# Mopq.net
KiCad netlist of a schematic drawn in Altium Designer
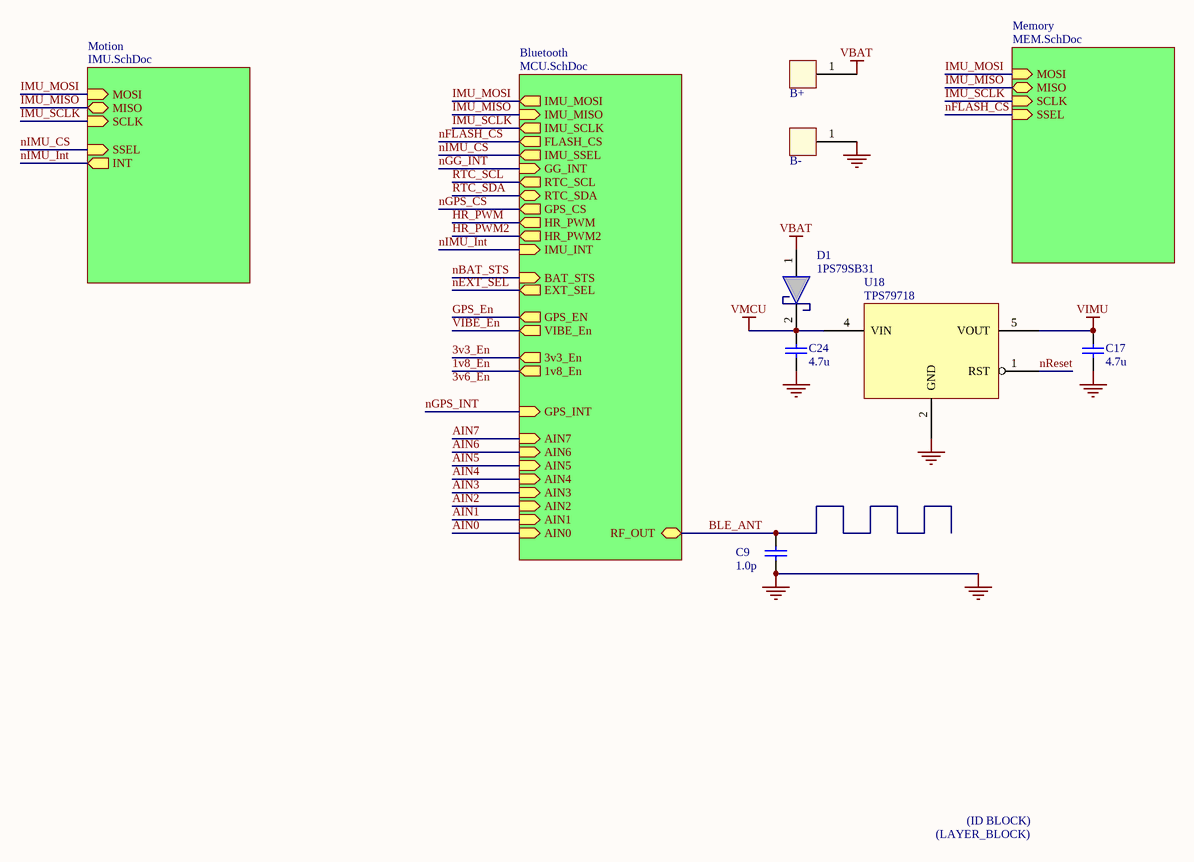
[diagram p0: Mopq.SchDoc]

(export (version "E")
  (design (tool "Eeschema 10.0.6"))
  (components
    (comp (ref "*")
      (value "LAYER_BLOCK")
      (footprint "Layer Stackup")
      (libsource (lib "Hello") (part "LAYER_BLOCK"))
    )
    (comp (ref "B+")
      (value "5016")
      (footprint "TP0875x050")
      (description "Single-pad test point")
      (libsource (lib "Mopd") (part "5016"))
    )
    (comp (ref "B-")
      (value "5016")
      (footprint "TP0875x050")
      (description "Single-pad test point")
      (libsource (lib "Mopd") (part "5016"))
    )
    (comp (ref "C9")
      (value "1.0p")
      (footprint "CAP0402")
      (description "Chip capacitor")
      (fields (field (name "TOLERANCE") "5 %") (field (name "VOLTAGE") "16V"))
      (libsource (lib "Hello") (part "C_2200p_5_16_STD_0402"))
    )
    (comp (ref "C17")
      (value "4.7u")
      (footprint "CAP0402")
      (description "Chip capacitor")
      (fields (field (name "TOLERANCE") "10%") (field (name "VOLTAGE") "10V"))
      (libsource (lib "Hello") (part "C_4.7u_10_10_JB_0402"))
    )
    (comp (ref "C24")
      (value "4.7u")
      (footprint "CAP0402")
      (description "Chip capacitor")
      (fields (field (name "TOLERANCE") "10%") (field (name "VOLTAGE") "10V"))
      (libsource (lib "Hello") (part "C_4.7u_10_10_JB_0402"))
    )
    (comp (ref "D1")
      (value "1PS79SB31")
      (footprint "SOD-523")
      (description "Schottky diode, 30V 200mA")
      (libsource (lib "Hello") (part "1PS79SB31"))
    )
    (comp (ref "ID1") (value "ID_BLOCK") (footprint "Hello Band") (libsource (lib "Hello") (part "ID_BLOCK")))
    (comp (ref "U18")
      (value "TPS79718")
      (footprint "SOT65P212X110-5N")
      (description "LDO 1.8V SC70-5")
      (libsource (lib "dykes") (part "TPS79718DCK"))
    )
  )
  (nets
    (net (code "12") (name "/BLE_ANT") (class "Default")
      (node (ref "C9") (pin "2") (pinfunction "2_2") (pintype "passive"))
    )
    (net (code "30") (name "/nReset") (class "Default")
      (node (ref "U18") (pin "1") (pinfunction "RST_1") (pintype "open_collector"))
    )
    (net (code "31") (name "GND") (class "Default")
      (node (ref "B-") (pin "1") (pinfunction "1_1") (pintype "passive"))
      (node (ref "C17") (pin "1") (pinfunction "1_1") (pintype "passive"))
      (node (ref "C24") (pin "1") (pinfunction "1_1") (pintype "passive"))
      (node (ref "C9") (pin "1") (pinfunction "1_1") (pintype "passive"))
      (node (ref "U18") (pin "2") (pinfunction "GND_2") (pintype "power_in"))
    )
    (net (code "32") (name "VBAT") (class "Default")
      (node (ref "B+") (pin "1") (pinfunction "1_1") (pintype "passive"))
      (node (ref "D1") (pin "1") (pinfunction "Anode_1") (pintype "passive"))
    )
    (net (code "33") (name "VIMU") (class "Default")
      (node (ref "C17") (pin "2") (pinfunction "2_2") (pintype "passive"))
      (node (ref "U18") (pin "5") (pinfunction "VOUT_5") (pintype "power_in"))
    )
    (net (code "34") (name "VMCU") (class "Default")
      (node (ref "C24") (pin "2") (pinfunction "2_2") (pintype "passive"))
      (node (ref "D1") (pin "2") (pinfunction "Cathode_2") (pintype "passive"))
      (node (ref "U18") (pin "4") (pinfunction "VIN_4") (pintype "power_in"))
    )
  )
)
